# 555_boost_converter_fixed_gain.net
KiCad netlist of a schematic drawn in EAGLE
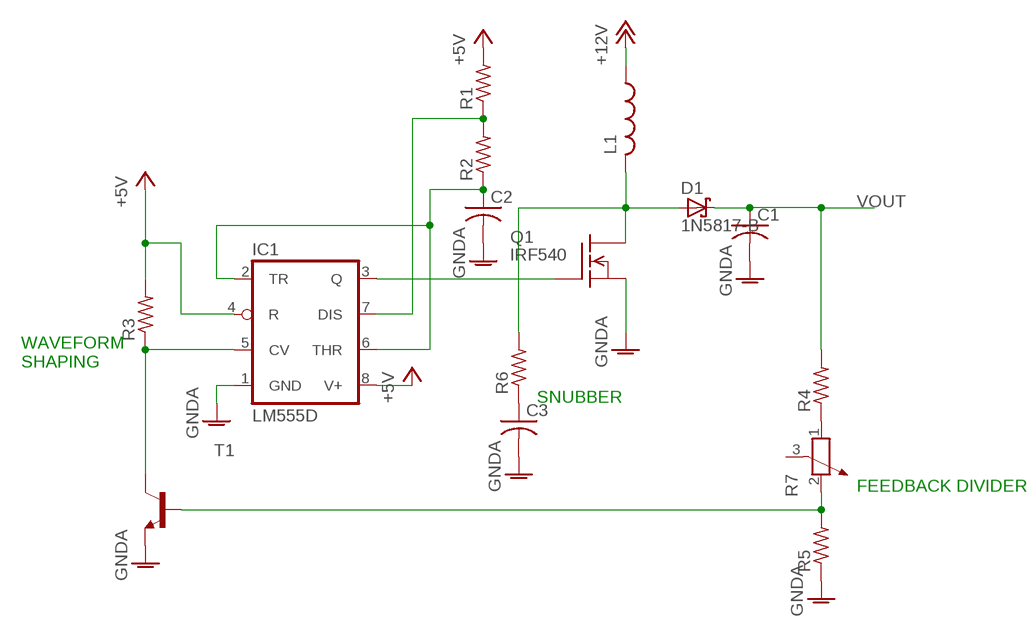
[diagram p0: schematic, sheet 1]

(export (version "E")
  (design (tool "Eeschema 10.0.6"))
  (components
    (comp (ref "C1")
      (value "C-USC0805")
      (footprint "eagle-import:C0805")
      (libsource (lib "eagle-import") (part "C-USC0805"))
    )
    (comp (ref "C2")
      (value "C-USC0805")
      (footprint "eagle-import:C0805")
      (libsource (lib "eagle-import") (part "C-USC0805"))
    )
    (comp (ref "C3")
      (value "C-USC0805")
      (footprint "eagle-import:C0805")
      (libsource (lib "eagle-import") (part "C-USC0805"))
    )
    (comp (ref "D1")
      (value "1N5817-B")
      (footprint "eagle-import:DO41-7.6")
      (libsource (lib "eagle-import") (part "1N5817-B"))
    )
    (comp (ref "IC1")
      (value "LM555D")
      (footprint "eagle-import:SO08")
      (libsource (lib "eagle-import") (part "555DLM"))
    )
    (comp (ref "L1")
      (value "L-USTJ3-U2")
      (footprint "eagle-import:TJ3-U2")
      (libsource (lib "eagle-import") (part "L-USTJ3-U2"))
    )
    (comp (ref "Q1")
      (value "IRF540")
      (footprint "eagle-import:TO220")
      (libsource (lib "eagle-import") (part "IRF540"))
    )
    (comp (ref "R1")
      (value "R-US_R0805")
      (footprint "eagle-import:R0805")
      (libsource (lib "eagle-import") (part "R-US_R0805"))
    )
    (comp (ref "R2")
      (value "R-US_R0805")
      (footprint "eagle-import:R0805")
      (libsource (lib "eagle-import") (part "R-US_R0805"))
    )
    (comp (ref "R3")
      (value "R-US_R0805")
      (footprint "eagle-import:R0805")
      (libsource (lib "eagle-import") (part "R-US_R0805"))
    )
    (comp (ref "R4")
      (value "R-US_R0805")
      (footprint "eagle-import:R0805")
      (libsource (lib "eagle-import") (part "R-US_R0805"))
    )
    (comp (ref "R5")
      (value "R-US_R0805")
      (footprint "eagle-import:R0805")
      (libsource (lib "eagle-import") (part "R-US_R0805"))
    )
    (comp (ref "R6")
      (value "R-US_R0805")
      (footprint "eagle-import:R0805")
      (libsource (lib "eagle-import") (part "R-US_R0805"))
    )
    (comp (ref "R7")
      (value "POTENTIOMETER_PT_SPIN")
      (footprint "eagle-import:PT-SPIN")
      (libsource (lib "eagle-import") (part "POTENTIOMETER_PT_SPIN"))
    )
    (comp (ref "T1")
      (value "2N2222-NPN-TO92-EBC")
      (footprint "eagle-import:TO92-EBC")
      (libsource (lib "eagle-import") (part "-NPN-TO92-EBC2N2222"))
    )
  )
  (nets
    (net (code "1") (name "+5V") (class "Default")
      (node (ref "IC1") (pin "4") (pinfunction "R_4") (pintype "input"))
      (node (ref "IC1") (pin "8") (pinfunction "V+_8") (pintype "power_in"))
      (node (ref "R1") (pin "2") (pinfunction "2_2") (pintype "passive"))
      (node (ref "R3") (pin "2") (pinfunction "2_2") (pintype "passive"))
    )
    (net (code "2") (name "+12V") (class "Default")
      (node (ref "L1") (pin "1") (pinfunction "1_1") (pintype "passive"))
    )
    (net (code "3") (name "/VOUT") (class "Default")
      (node (ref "C1") (pin "1") (pinfunction "1_1") (pintype "passive"))
      (node (ref "D1") (pin "C") (pinfunction "C_C") (pintype "passive"))
      (node (ref "R4") (pin "2") (pinfunction "2_2") (pintype "passive"))
    )
    (net (code "4") (name "GNDA") (class "Default")
      (node (ref "C1") (pin "2") (pinfunction "2_2") (pintype "passive"))
      (node (ref "C2") (pin "2") (pinfunction "2_2") (pintype "passive"))
      (node (ref "C3") (pin "2") (pinfunction "2_2") (pintype "passive"))
      (node (ref "IC1") (pin "1") (pinfunction "GND_1") (pintype "power_in"))
      (node (ref "Q1") (pin "3") (pinfunction "S_3") (pintype "passive"))
      (node (ref "R5") (pin "1") (pinfunction "1_1") (pintype "passive"))
      (node (ref "T1") (pin "E") (pinfunction "E_E") (pintype "passive"))
    )
    (net (code "5") (name "Net-(C3-Pad1)") (class "Default")
      (node (ref "C3") (pin "1") (pinfunction "1_1") (pintype "passive"))
      (node (ref "R6") (pin "1") (pinfunction "1_1") (pintype "passive"))
    )
    (net (code "6") (name "Net-(IC1-CV)") (class "Default")
      (node (ref "IC1") (pin "5") (pinfunction "CV_5") (pintype "input"))
      (node (ref "R3") (pin "1") (pinfunction "1_1") (pintype "passive"))
      (node (ref "T1") (pin "C") (pinfunction "C_C") (pintype "passive"))
    )
    (net (code "7") (name "Net-(IC1-DIS)") (class "Default")
      (node (ref "IC1") (pin "7") (pinfunction "DIS_7") (pintype "input"))
      (node (ref "R1") (pin "1") (pinfunction "1_1") (pintype "passive"))
      (node (ref "R2") (pin "2") (pinfunction "2_2") (pintype "passive"))
    )
    (net (code "8") (name "Net-(IC1-Q)") (class "Default")
      (node (ref "IC1") (pin "3") (pinfunction "Q_3") (pintype "output"))
      (node (ref "Q1") (pin "1") (pinfunction "G_1") (pintype "passive"))
    )
    (net (code "9") (name "Net-(IC1-THR)") (class "Default")
      (node (ref "C2") (pin "1") (pinfunction "1_1") (pintype "passive"))
      (node (ref "IC1") (pin "2") (pinfunction "TR_2") (pintype "input"))
      (node (ref "IC1") (pin "6") (pinfunction "THR_6") (pintype "input"))
      (node (ref "R2") (pin "1") (pinfunction "1_1") (pintype "passive"))
    )
    (net (code "10") (name "Net-(Q1-D)") (class "Default")
      (node (ref "D1") (pin "A") (pinfunction "A_A") (pintype "passive"))
      (node (ref "L1") (pin "2") (pinfunction "2_2") (pintype "passive"))
      (node (ref "Q1") (pin "2") (pinfunction "D_2") (pintype "passive"))
      (node (ref "R6") (pin "2") (pinfunction "2_2") (pintype "passive"))
    )
    (net (code "11") (name "Net-(R4-Pad1)") (class "Default")
      (node (ref "R4") (pin "1") (pinfunction "1_1") (pintype "passive"))
      (node (ref "R7") (pin "1") (pinfunction "1_1") (pintype "passive"))
    )
    (net (code "12") (name "Net-(R5-Pad2)") (class "Default")
      (node (ref "R5") (pin "2") (pinfunction "2_2") (pintype "passive"))
      (node (ref "R7") (pin "2") (pinfunction "2_2") (pintype "passive"))
      (node (ref "T1") (pin "B") (pinfunction "B_B") (pintype "passive"))
    )
    (net (code "13") (name "unconnected-(R7-Pad3)") (class "Default")
      (node (ref "R7") (pin "3") (pinfunction "3_3") (pintype "passive"))
    )
  )
)
